# easyeda.net
KiCad netlist of a schematic drawn in EasyEDA
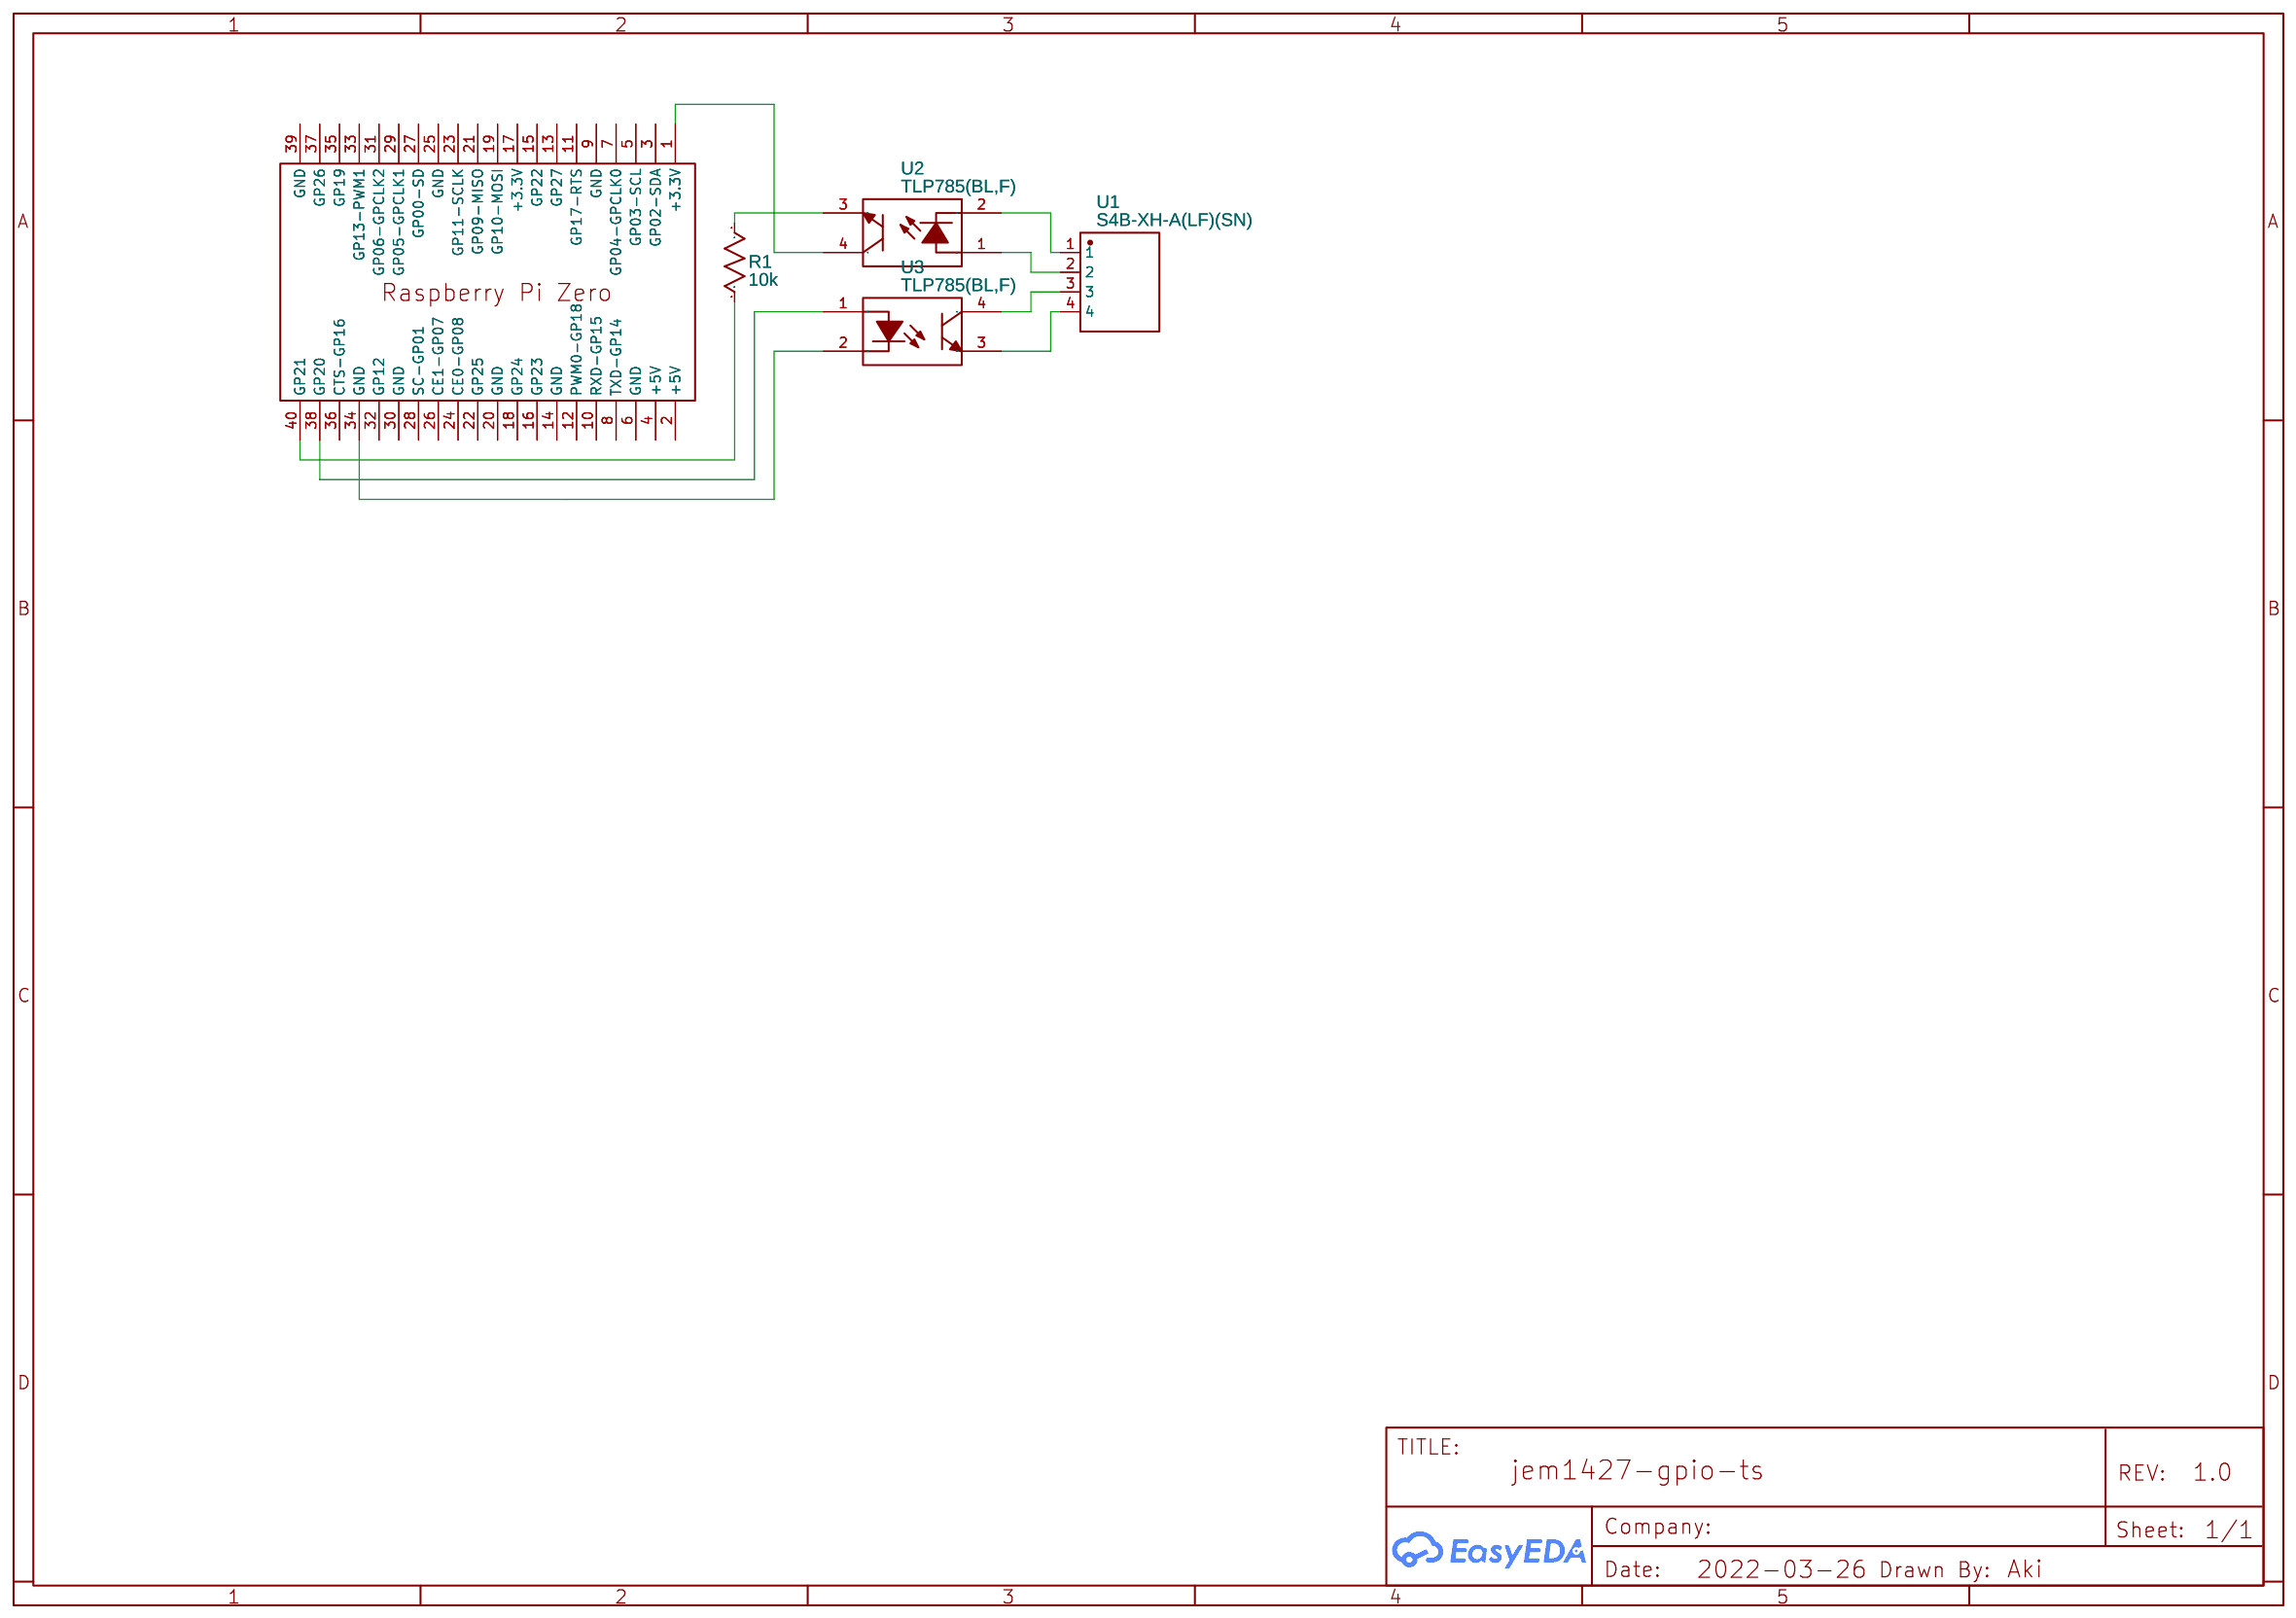
[diagram p0: schematic sheet]

(export (version "E")
  (design (tool "Eeschema 10.0.6"))
  (components
    (comp (ref "R1") (value "10k") (libsource (lib "") (part "R_0201_US")))
    (comp (ref "RPI1")
      (value "Raspberry Pi Zero")
      (fields
        (field (name "Manufacturer Part") "Raspberry Pi Zero WH")
        (field (name "Manufacturer") "Raspberry Pi Foundation")
      )
      (libsource (lib "") (part "Raspberry Pi Zero"))
    )
    (comp (ref "U1")
      (value "S4B-XH-A(LF)(SN)")
      (fields
        (field (name "Manufacturer Part") "B4B-XH-A(LF)(SN)")
        (field (name "Manufacturer") "JST Sales America")
      )
      (libsource (lib "") (part "B4B-XH-A(LF)(SN)"))
    )
    (comp (ref "U2")
      (value "TLP785(BL,F)")
      (fields (field (name "Manufacturer") "TOSHIBA"))
      (libsource (lib "") (part "TLP785(BL,F)_1"))
    )
    (comp (ref "U3")
      (value "TLP785(BL,F)")
      (fields (field (name "Manufacturer") "TOSHIBA"))
      (libsource (lib "") (part "TLP785(BL,F)"))
    )
  )
  (nets
    (net (code "1") (name "Net-(R1-Pad1)") (class "Default")
      (node (ref "R1") (pin "1") (pinfunction "1_1") (pintype "unspecified"))
      (node (ref "U2") (pin "3") (pinfunction "3_3") (pintype "unspecified"))
    )
    (net (code "2") (name "Net-(RPI1-+3.3V-Pad1)") (class "Default")
      (node (ref "RPI1") (pin "1") (pinfunction "+3.3V_1") (pintype "unspecified"))
      (node (ref "U2") (pin "4") (pinfunction "4_4") (pintype "unspecified"))
    )
    (net (code "3") (name "Net-(RPI1-GND-Pad34)") (class "Default")
      (node (ref "RPI1") (pin "34") (pinfunction "GND_34") (pintype "unspecified"))
      (node (ref "U3") (pin "2") (pinfunction "2_2") (pintype "unspecified"))
    )
    (net (code "4") (name "Net-(RPI1-GP20)") (class "Default")
      (node (ref "RPI1") (pin "38") (pinfunction "GP20_38") (pintype "unspecified"))
      (node (ref "U3") (pin "1") (pinfunction "1_1") (pintype "unspecified"))
    )
    (net (code "5") (name "Net-(RPI1-GP21)") (class "Default")
      (node (ref "R1") (pin "2") (pinfunction "2_2") (pintype "unspecified"))
      (node (ref "RPI1") (pin "40") (pinfunction "GP21_40") (pintype "unspecified"))
    )
    (net (code "6") (name "Net-(U1-Pad1)") (class "Default")
      (node (ref "U1") (pin "1") (pinfunction "1_1") (pintype "unspecified"))
      (node (ref "U2") (pin "2") (pinfunction "2_2") (pintype "unspecified"))
    )
    (net (code "7") (name "Net-(U1-Pad2)") (class "Default")
      (node (ref "U1") (pin "2") (pinfunction "2_2") (pintype "unspecified"))
      (node (ref "U2") (pin "1") (pinfunction "1_1") (pintype "unspecified"))
    )
    (net (code "8") (name "Net-(U1-Pad3)") (class "Default")
      (node (ref "U1") (pin "3") (pinfunction "3_3") (pintype "unspecified"))
      (node (ref "U3") (pin "4") (pinfunction "4_4") (pintype "unspecified"))
    )
    (net (code "9") (name "Net-(U1-Pad4)") (class "Default")
      (node (ref "U1") (pin "4") (pinfunction "4_4") (pintype "unspecified"))
      (node (ref "U3") (pin "3") (pinfunction "3_3") (pintype "unspecified"))
    )
    (net (code "10") (name "unconnected-(RPI1-+3.3V-Pad17)") (class "Default")
      (node (ref "RPI1") (pin "17") (pinfunction "+3.3V_17") (pintype "unspecified"))
    )
    (net (code "11") (name "unconnected-(RPI1-+5V-Pad2)") (class "Default")
      (node (ref "RPI1") (pin "2") (pinfunction "+5V_2") (pintype "unspecified"))
    )
    (net (code "12") (name "unconnected-(RPI1-+5V-Pad4)") (class "Default")
      (node (ref "RPI1") (pin "4") (pinfunction "+5V_4") (pintype "unspecified"))
    )
    (net (code "13") (name "unconnected-(RPI1-CE0-GP08-Pad24)") (class "Default")
      (node (ref "RPI1") (pin "24") (pinfunction "CE0-GP08_24") (pintype "unspecified"))
    )
    (net (code "14") (name "unconnected-(RPI1-CE1-GP07-Pad26)") (class "Default")
      (node (ref "RPI1") (pin "26") (pinfunction "CE1-GP07_26") (pintype "unspecified"))
    )
    (net (code "15") (name "unconnected-(RPI1-CTS-GP16-Pad36)") (class "Default")
      (node (ref "RPI1") (pin "36") (pinfunction "CTS-GP16_36") (pintype "unspecified"))
    )
    (net (code "16") (name "unconnected-(RPI1-GND-Pad6)") (class "Default")
      (node (ref "RPI1") (pin "6") (pinfunction "GND_6") (pintype "unspecified"))
    )
    (net (code "17") (name "unconnected-(RPI1-GND-Pad9)") (class "Default")
      (node (ref "RPI1") (pin "9") (pinfunction "GND_9") (pintype "unspecified"))
    )
    (net (code "18") (name "unconnected-(RPI1-GND-Pad14)") (class "Default")
      (node (ref "RPI1") (pin "14") (pinfunction "GND_14") (pintype "unspecified"))
    )
    (net (code "19") (name "unconnected-(RPI1-GND-Pad20)") (class "Default")
      (node (ref "RPI1") (pin "20") (pinfunction "GND_20") (pintype "unspecified"))
    )
    (net (code "20") (name "unconnected-(RPI1-GND-Pad25)") (class "Default")
      (node (ref "RPI1") (pin "25") (pinfunction "GND_25") (pintype "unspecified"))
    )
    (net (code "21") (name "unconnected-(RPI1-GND-Pad30)") (class "Default")
      (node (ref "RPI1") (pin "30") (pinfunction "GND_30") (pintype "unspecified"))
    )
    (net (code "22") (name "unconnected-(RPI1-GND-Pad39)") (class "Default")
      (node (ref "RPI1") (pin "39") (pinfunction "GND_39") (pintype "unspecified"))
    )
    (net (code "23") (name "unconnected-(RPI1-GP00-SD-Pad27)") (class "Default")
      (node (ref "RPI1") (pin "27") (pinfunction "GP00-SD_27") (pintype "unspecified"))
    )
    (net (code "24") (name "unconnected-(RPI1-GP02-SDA-Pad3)") (class "Default")
      (node (ref "RPI1") (pin "3") (pinfunction "GP02-SDA_3") (pintype "unspecified"))
    )
    (net (code "25") (name "unconnected-(RPI1-GP03-SCL-Pad5)") (class "Default")
      (node (ref "RPI1") (pin "5") (pinfunction "GP03-SCL_5") (pintype "unspecified"))
    )
    (net (code "26") (name "unconnected-(RPI1-GP04-GPCLK0-Pad7)") (class "Default")
      (node (ref "RPI1") (pin "7") (pinfunction "GP04-GPCLK0_7") (pintype "unspecified"))
    )
    (net (code "27") (name "unconnected-(RPI1-GP05-GPCLK1-Pad29)") (class "Default")
      (node (ref "RPI1") (pin "29") (pinfunction "GP05-GPCLK1_29") (pintype "unspecified"))
    )
    (net (code "28") (name "unconnected-(RPI1-GP06-GPCLK2-Pad31)") (class "Default")
      (node (ref "RPI1") (pin "31") (pinfunction "GP06-GPCLK2_31") (pintype "unspecified"))
    )
    (net (code "29") (name "unconnected-(RPI1-GP09-MISO-Pad21)") (class "Default")
      (node (ref "RPI1") (pin "21") (pinfunction "GP09-MISO_21") (pintype "unspecified"))
    )
    (net (code "30") (name "unconnected-(RPI1-GP10-MOSI-Pad19)") (class "Default")
      (node (ref "RPI1") (pin "19") (pinfunction "GP10-MOSI_19") (pintype "unspecified"))
    )
    (net (code "31") (name "unconnected-(RPI1-GP11-SCLK-Pad23)") (class "Default")
      (node (ref "RPI1") (pin "23") (pinfunction "GP11-SCLK_23") (pintype "unspecified"))
    )
    (net (code "32") (name "unconnected-(RPI1-GP12-Pad32)") (class "Default")
      (node (ref "RPI1") (pin "32") (pinfunction "GP12_32") (pintype "unspecified"))
    )
    (net (code "33") (name "unconnected-(RPI1-GP13-PWM1-Pad33)") (class "Default")
      (node (ref "RPI1") (pin "33") (pinfunction "GP13-PWM1_33") (pintype "unspecified"))
    )
    (net (code "34") (name "unconnected-(RPI1-GP17-RTS-Pad11)") (class "Default")
      (node (ref "RPI1") (pin "11") (pinfunction "GP17-RTS_11") (pintype "unspecified"))
    )
    (net (code "35") (name "unconnected-(RPI1-GP19-Pad35)") (class "Default")
      (node (ref "RPI1") (pin "35") (pinfunction "GP19_35") (pintype "unspecified"))
    )
    (net (code "36") (name "unconnected-(RPI1-GP22-Pad15)") (class "Default")
      (node (ref "RPI1") (pin "15") (pinfunction "GP22_15") (pintype "unspecified"))
    )
    (net (code "37") (name "unconnected-(RPI1-GP23-Pad16)") (class "Default")
      (node (ref "RPI1") (pin "16") (pinfunction "GP23_16") (pintype "unspecified"))
    )
    (net (code "38") (name "unconnected-(RPI1-GP24-Pad18)") (class "Default")
      (node (ref "RPI1") (pin "18") (pinfunction "GP24_18") (pintype "unspecified"))
    )
    (net (code "39") (name "unconnected-(RPI1-GP25-Pad22)") (class "Default")
      (node (ref "RPI1") (pin "22") (pinfunction "GP25_22") (pintype "unspecified"))
    )
    (net (code "40") (name "unconnected-(RPI1-GP26-Pad37)") (class "Default")
      (node (ref "RPI1") (pin "37") (pinfunction "GP26_37") (pintype "unspecified"))
    )
    (net (code "41") (name "unconnected-(RPI1-GP27-Pad13)") (class "Default")
      (node (ref "RPI1") (pin "13") (pinfunction "GP27_13") (pintype "unspecified"))
    )
    (net (code "42") (name "unconnected-(RPI1-PWM0-GP18-Pad12)") (class "Default")
      (node (ref "RPI1") (pin "12") (pinfunction "PWM0-GP18_12") (pintype "unspecified"))
    )
    (net (code "43") (name "unconnected-(RPI1-RXD-GP15-Pad10)") (class "Default")
      (node (ref "RPI1") (pin "10") (pinfunction "RXD-GP15_10") (pintype "unspecified"))
    )
    (net (code "44") (name "unconnected-(RPI1-SC-GP01-Pad28)") (class "Default")
      (node (ref "RPI1") (pin "28") (pinfunction "SC-GP01_28") (pintype "unspecified"))
    )
    (net (code "45") (name "unconnected-(RPI1-TXD-GP14-Pad8)") (class "Default")
      (node (ref "RPI1") (pin "8") (pinfunction "TXD-GP14_8") (pintype "unspecified"))
    )
  )
)
